# SenseSing-prog-adaptor-v0_2.net
KiCad netlist of a schematic drawn in EAGLE
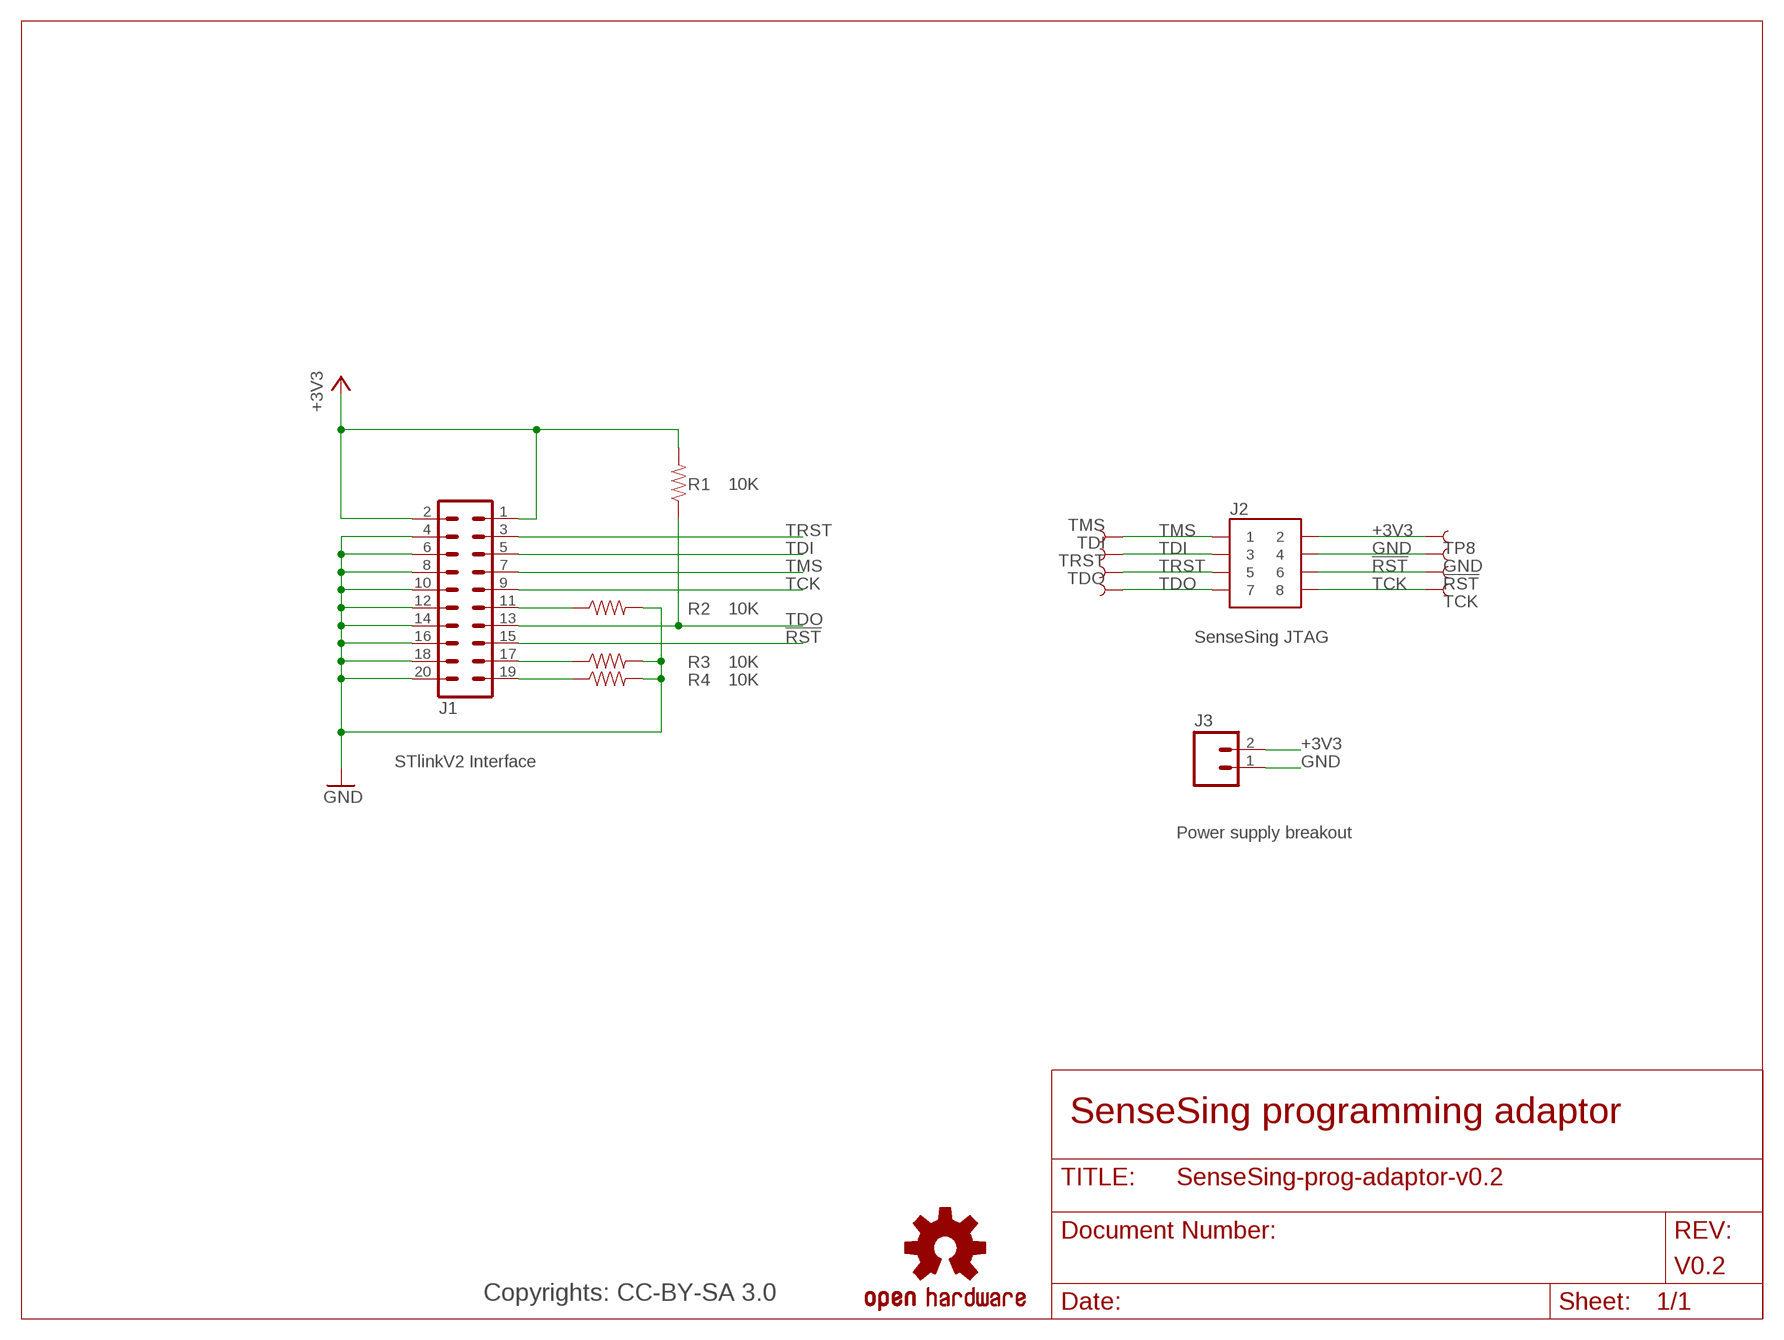
[diagram p0: schematic, sheet 1]

(export (version "E")
  (design (tool "Eeschema 10.0.6"))
  (components
    (comp (ref "!RST")
      (value "TEST-POINT3")
      (footprint "eagle-import:PAD.03X.03")
      (libsource (lib "eagle-import") (part "TEST-POINT3"))
    )
    (comp (ref "GND")
      (value "TEST-POINT3")
      (footprint "eagle-import:PAD.03X.03")
      (libsource (lib "eagle-import") (part "TEST-POINT3"))
    )
    (comp (ref "J1")
      (value "ML20")
      (footprint "eagle-import:ML20")
      (libsource (lib "eagle-import") (part "ML20"))
    )
    (comp (ref "J2")
      (value "JTAG_CONNECTOR")
      (footprint "eagle-import:JTAG_DIP")
      (libsource (lib "eagle-import") (part "JTAG_CONNECTOR"))
    )
    (comp (ref "J3")
      (value "M02PTH")
      (footprint "eagle-import:1X02")
      (libsource (lib "eagle-import") (part "M02PTH"))
    )
    (comp (ref "LOGO1")
      (value "OSHW-LOGOPAD")
      (footprint "eagle-import:OSHW-LOGO-M-PAD")
      (libsource (lib "eagle-import") (part "OSHW-LOGOPAD"))
    )
    (comp (ref "R1")
      (value "10K")
      (footprint "eagle-import:AXIAL-0.3")
      (libsource (lib "eagle-import") (part "RESISTORAXIAL-0.3"))
    )
    (comp (ref "R2")
      (value "10K")
      (footprint "eagle-import:AXIAL-0.3")
      (libsource (lib "eagle-import") (part "RESISTORAXIAL-0.3"))
    )
    (comp (ref "R3")
      (value "10K")
      (footprint "eagle-import:AXIAL-0.3")
      (libsource (lib "eagle-import") (part "RESISTORAXIAL-0.3"))
    )
    (comp (ref "R4")
      (value "10K")
      (footprint "eagle-import:AXIAL-0.3")
      (libsource (lib "eagle-import") (part "RESISTORAXIAL-0.3"))
    )
    (comp (ref "TCK")
      (value "TEST-POINT3")
      (footprint "eagle-import:PAD.03X.03")
      (libsource (lib "eagle-import") (part "TEST-POINT3"))
    )
    (comp (ref "TDI")
      (value "TEST-POINT3")
      (footprint "eagle-import:PAD.03X.03")
      (libsource (lib "eagle-import") (part "TEST-POINT3"))
    )
    (comp (ref "TDO")
      (value "TEST-POINT3")
      (footprint "eagle-import:PAD.03X.03")
      (libsource (lib "eagle-import") (part "TEST-POINT3"))
    )
    (comp (ref "TMS")
      (value "TEST-POINT3")
      (footprint "eagle-import:PAD.03X.03")
      (libsource (lib "eagle-import") (part "TEST-POINT3"))
    )
    (comp (ref "TP8")
      (value "TEST-POINT3")
      (footprint "eagle-import:PAD.03X.03")
      (libsource (lib "eagle-import") (part "TEST-POINT3"))
    )
    (comp (ref "TRST")
      (value "TEST-POINT3")
      (footprint "eagle-import:PAD.03X.03")
      (libsource (lib "eagle-import") (part "TEST-POINT3"))
    )
  )
  (nets
    (net (code "1") (name "+3V3") (class "Default")
      (node (ref "J1") (pin "1") (pinfunction "1_1") (pintype "passive"))
      (node (ref "J1") (pin "2") (pinfunction "2_2") (pintype "passive"))
      (node (ref "J2") (pin "2") (pinfunction "2_2") (pintype "bidirectional"))
      (node (ref "J3") (pin "2") (pinfunction "2_2") (pintype "passive"))
      (node (ref "R1") (pin "P$2") (pinfunction "2_P$2") (pintype "passive"))
      (node (ref "TP8") (pin "P$1") (pinfunction "1_P$1") (pintype "bidirectional"))
    )
    (net (code "2") (name "/TCK") (class "Default")
      (node (ref "J1") (pin "9") (pinfunction "9_9") (pintype "passive"))
      (node (ref "J2") (pin "8") (pinfunction "8_8") (pintype "bidirectional"))
      (node (ref "TCK") (pin "P$1") (pinfunction "1_P$1") (pintype "bidirectional"))
    )
    (net (code "3") (name "/TDI") (class "Default")
      (node (ref "J1") (pin "5") (pinfunction "5_5") (pintype "passive"))
      (node (ref "J2") (pin "3") (pinfunction "3_3") (pintype "bidirectional"))
      (node (ref "TDI") (pin "P$1") (pinfunction "1_P$1") (pintype "bidirectional"))
    )
    (net (code "4") (name "/TDO") (class "Default")
      (node (ref "J1") (pin "13") (pinfunction "13_13") (pintype "passive"))
      (node (ref "J2") (pin "7") (pinfunction "7_7") (pintype "bidirectional"))
      (node (ref "R1") (pin "P$1") (pinfunction "1_P$1") (pintype "passive"))
      (node (ref "TDO") (pin "P$1") (pinfunction "1_P$1") (pintype "bidirectional"))
    )
    (net (code "5") (name "/TMS") (class "Default")
      (node (ref "J1") (pin "7") (pinfunction "7_7") (pintype "passive"))
      (node (ref "J2") (pin "1") (pinfunction "1_1") (pintype "bidirectional"))
      (node (ref "TMS") (pin "P$1") (pinfunction "1_P$1") (pintype "bidirectional"))
    )
    (net (code "6") (name "/TRST") (class "Default")
      (node (ref "J1") (pin "3") (pinfunction "3_3") (pintype "passive"))
      (node (ref "J2") (pin "5") (pinfunction "5_5") (pintype "bidirectional"))
      (node (ref "TRST") (pin "P$1") (pinfunction "1_P$1") (pintype "bidirectional"))
    )
    (net (code "7") (name "/~{RST}") (class "Default")
      (node (ref "!RST") (pin "P$1") (pinfunction "1_P$1") (pintype "bidirectional"))
      (node (ref "J1") (pin "15") (pinfunction "15_15") (pintype "passive"))
      (node (ref "J2") (pin "6") (pinfunction "6_6") (pintype "bidirectional"))
    )
    (net (code "8") (name "GND") (class "Default")
      (node (ref "GND") (pin "P$1") (pinfunction "1_P$1") (pintype "bidirectional"))
      (node (ref "J1") (pin "10") (pinfunction "10_10") (pintype "passive"))
      (node (ref "J1") (pin "12") (pinfunction "12_12") (pintype "passive"))
      (node (ref "J1") (pin "14") (pinfunction "14_14") (pintype "passive"))
      (node (ref "J1") (pin "16") (pinfunction "16_16") (pintype "passive"))
      (node (ref "J1") (pin "18") (pinfunction "18_18") (pintype "passive"))
      (node (ref "J1") (pin "20") (pinfunction "20_20") (pintype "passive"))
      (node (ref "J1") (pin "4") (pinfunction "4_4") (pintype "passive"))
      (node (ref "J1") (pin "6") (pinfunction "6_6") (pintype "passive"))
      (node (ref "J1") (pin "8") (pinfunction "8_8") (pintype "passive"))
      (node (ref "J2") (pin "4") (pinfunction "4_4") (pintype "bidirectional"))
      (node (ref "J3") (pin "1") (pinfunction "1_1") (pintype "passive"))
      (node (ref "R2") (pin "P$2") (pinfunction "2_P$2") (pintype "passive"))
      (node (ref "R3") (pin "P$2") (pinfunction "2_P$2") (pintype "passive"))
      (node (ref "R4") (pin "P$2") (pinfunction "2_P$2") (pintype "passive"))
    )
    (net (code "9") (name "Net-(R2-1)") (class "Default")
      (node (ref "J1") (pin "11") (pinfunction "11_11") (pintype "passive"))
      (node (ref "R2") (pin "P$1") (pinfunction "1_P$1") (pintype "passive"))
    )
    (net (code "10") (name "Net-(R3-1)") (class "Default")
      (node (ref "J1") (pin "17") (pinfunction "17_17") (pintype "passive"))
      (node (ref "R3") (pin "P$1") (pinfunction "1_P$1") (pintype "passive"))
    )
    (net (code "11") (name "Net-(R4-1)") (class "Default")
      (node (ref "J1") (pin "19") (pinfunction "19_19") (pintype "passive"))
      (node (ref "R4") (pin "P$1") (pinfunction "1_P$1") (pintype "passive"))
    )
  )
)
